# DAC_Wenzel.net
KiCad netlist of a schematic drawn in Altium Designer
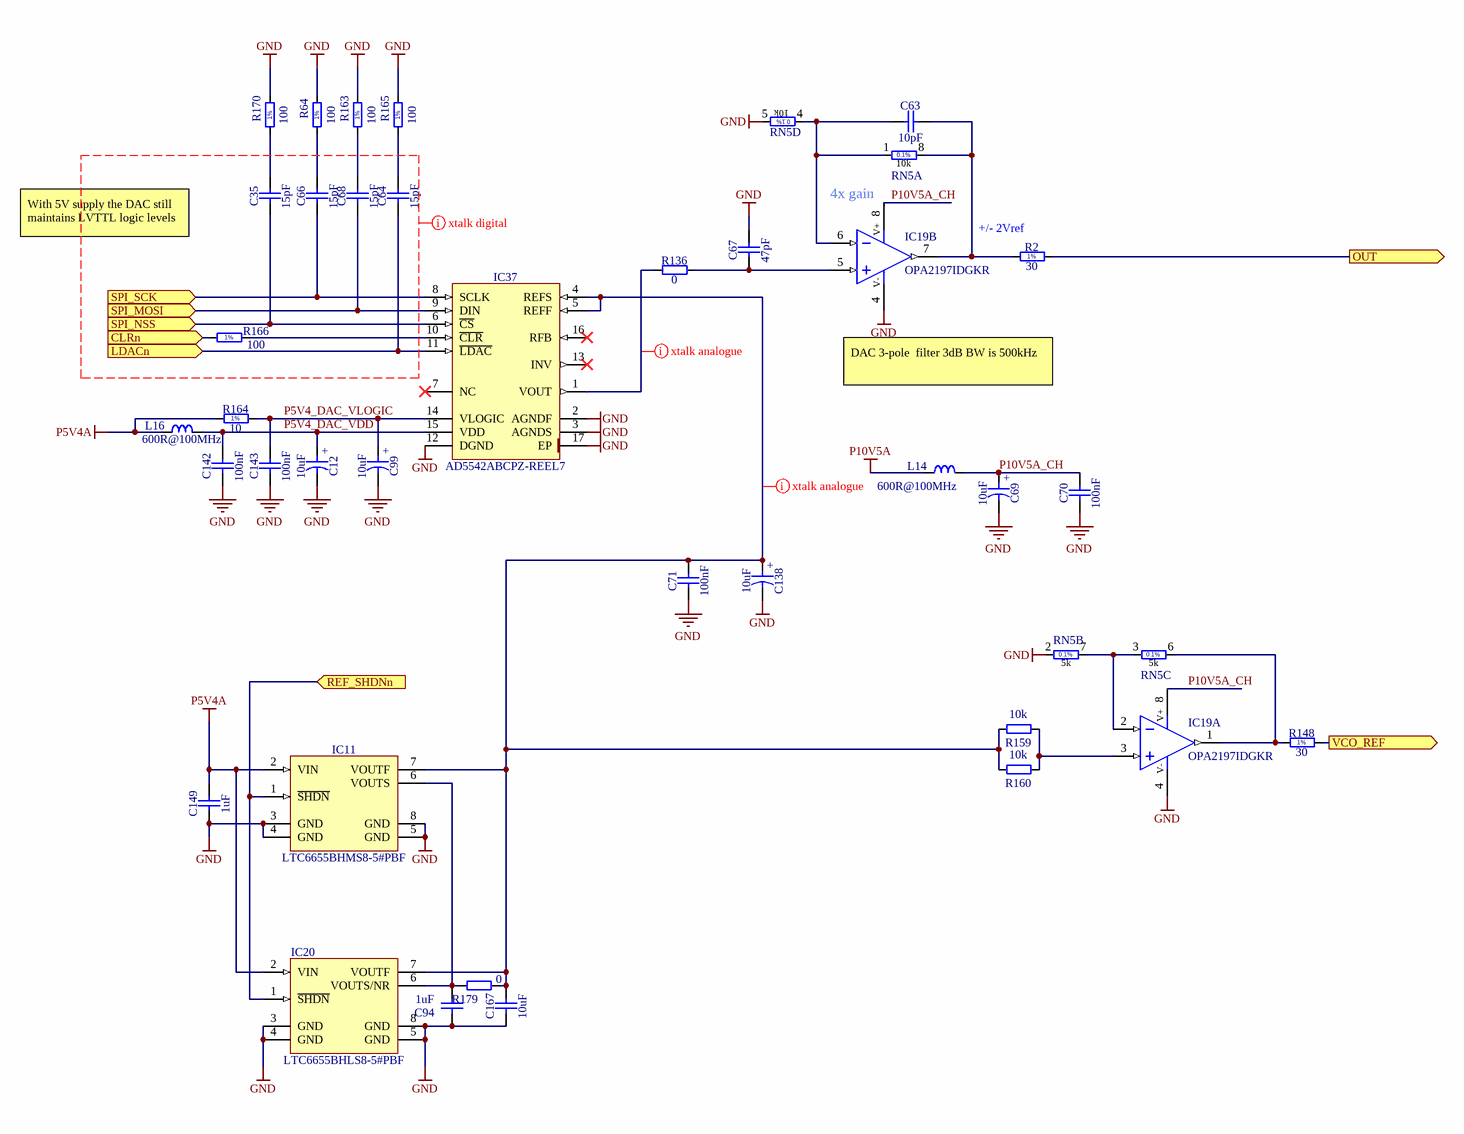
[diagram p0: DAC_Wenzel.SchDoc]

(export (version "E")
  (design (tool "Eeschema 10.0.6"))
  (components
    (comp (ref "C12")
      (value "10uF")
      (footprint "CAPMP3216X180N")
      (description "Polarised capacitor")
      (fields
        (field (name "PART NUMBER") "CTE3216-18_10UF_16V_20%_AVX_TCJ")
        (field (name "VOLTAGE") "16V")
        (field (name "AUTHOR") "CERN DEM JLC")
      )
      (libsource (lib "Capacitors") (part "Capacitor - polarized"))
    )
    (comp (ref "C35")
      (value "15pF")
      (footprint "CAPC1608X87N")
      (description "Non-polarised capacitor")
      (fields
        (field (name "PART NUMBER") "CC0603_15PF_50V_5%_NP0")
        (field (name "VOLTAGE") "50V")
        (field (name "AUTHOR") "CERN DEM JLC")
      )
      (libsource (lib "Capacitors") (part "Capacitor - non polarized"))
    )
    (comp (ref "C63")
      (value "10pF")
      (footprint "CAPC1005X55N")
      (description "Non-polarised capacitor")
      (fields
        (field (name "PART NUMBER") "CC0402_10PF_50V_5%_C0G")
        (field (name "VOLTAGE") "50V")
        (field (name "AUTHOR") "CERN DEM JLC")
      )
      (libsource (lib "Capacitors") (part "Capacitor - non polarized"))
    )
    (comp (ref "C64")
      (value "15pF")
      (footprint "CAPC1608X87N")
      (description "Non-polarised capacitor")
      (fields
        (field (name "PART NUMBER") "CC0603_15PF_50V_5%_NP0")
        (field (name "VOLTAGE") "50V")
        (field (name "AUTHOR") "CERN DEM JLC")
      )
      (libsource (lib "Capacitors") (part "Capacitor - non polarized"))
    )
    (comp (ref "C66")
      (value "15pF")
      (footprint "CAPC1608X87N")
      (description "Non-polarised capacitor")
      (fields
        (field (name "PART NUMBER") "CC0603_15PF_50V_5%_NP0")
        (field (name "VOLTAGE") "50V")
        (field (name "AUTHOR") "CERN DEM JLC")
      )
      (libsource (lib "Capacitors") (part "Capacitor - non polarized"))
    )
    (comp (ref "C67")
      (value "47pF")
      (footprint "CAPC1005X55N")
      (description "Non-polarised capacitor")
      (fields
        (field (name "PART NUMBER") "CC0402_47PF_50V_1%_C0G_MURATA_GJM1555C1H470FB01D")
        (field (name "VOLTAGE") "50V")
        (field (name "AUTHOR") "CERN DEM BC")
      )
      (libsource (lib "Capacitors") (part "Capacitor - non polarized"))
    )
    (comp (ref "C68")
      (value "15pF")
      (footprint "CAPC1608X87N")
      (description "Non-polarised capacitor")
      (fields
        (field (name "PART NUMBER") "CC0603_15PF_50V_5%_NP0")
        (field (name "VOLTAGE") "50V")
        (field (name "AUTHOR") "CERN DEM JLC")
      )
      (libsource (lib "Capacitors") (part "Capacitor - non polarized"))
    )
    (comp (ref "C69")
      (value "10uF")
      (footprint "CAPMP3216X180N")
      (description "Polarised capacitor")
      (fields
        (field (name "PART NUMBER") "CTE3216-18_10UF_16V_20%_AVX_TCJ")
        (field (name "VOLTAGE") "16V")
        (field (name "AUTHOR") "CERN DEM JLC")
      )
      (libsource (lib "Capacitors") (part "Capacitor - polarized"))
    )
    (comp (ref "C70")
      (value "100nF")
      (footprint "CAPC1005X55N")
      (description "Non-polarised capacitor")
      (fields
        (field (name "PART NUMBER") "CC0402_100NF_16V_10%_X7R")
        (field (name "VOLTAGE") "16V")
        (field (name "AUTHOR") "CERN DEM JLC")
      )
      (libsource (lib "Capacitors") (part "Capacitor - non polarized"))
    )
    (comp (ref "C71")
      (value "100nF")
      (footprint "CAPC1005X55N")
      (description "Non-polarised capacitor")
      (fields
        (field (name "PART NUMBER") "CC0402_100NF_16V_10%_X7R")
        (field (name "VOLTAGE") "16V")
        (field (name "AUTHOR") "CERN DEM JLC")
      )
      (libsource (lib "Capacitors") (part "Capacitor - non polarized"))
    )
    (comp (ref "C94")
      (value "1uF")
      (footprint "CAPC1608X87N")
      (description "Non-polarised capacitor")
      (fields
        (field (name "PART NUMBER") "CC0603_1UF_25V_10%_X7R")
        (field (name "VOLTAGE") "25V")
        (field (name "AUTHOR") "CERN DEM JLC")
      )
      (libsource (lib "Capacitors") (part "Capacitor - non polarized"))
    )
    (comp (ref "C99")
      (value "10uF")
      (footprint "CAPMP3216X180N")
      (description "Polarised capacitor")
      (fields
        (field (name "PART NUMBER") "CTE3216-18_10UF_16V_20%_AVX_TCJ")
        (field (name "VOLTAGE") "16V")
        (field (name "AUTHOR") "CERN DEM JLC")
      )
      (libsource (lib "Capacitors") (part "Capacitor - polarized"))
    )
    (comp (ref "C138")
      (value "10uF")
      (footprint "CAPMP3216X180N")
      (description "Polarised capacitor")
      (fields
        (field (name "PART NUMBER") "CTE3216-18_10UF_16V_20%_AVX_TCJ")
        (field (name "VOLTAGE") "16V")
        (field (name "AUTHOR") "CERN DEM JLC")
      )
      (libsource (lib "Capacitors") (part "Capacitor - polarized"))
    )
    (comp (ref "C142")
      (value "100nF")
      (footprint "CAPC1005X55N")
      (description "Non-polarised capacitor")
      (fields
        (field (name "PART NUMBER") "CC0402_100NF_16V_10%_X7R")
        (field (name "VOLTAGE") "16V")
        (field (name "AUTHOR") "CERN DEM JLC")
      )
      (libsource (lib "Capacitors") (part "Capacitor - non polarized"))
    )
    (comp (ref "C143")
      (value "100nF")
      (footprint "CAPC1005X55N")
      (description "Non-polarised capacitor")
      (fields
        (field (name "PART NUMBER") "CC0402_100NF_16V_10%_X7R")
        (field (name "VOLTAGE") "16V")
        (field (name "AUTHOR") "CERN DEM JLC")
      )
      (libsource (lib "Capacitors") (part "Capacitor - non polarized"))
    )
    (comp (ref "C149")
      (value "1uF")
      (footprint "CAPC1608X87N")
      (description "Non-polarised capacitor")
      (fields
        (field (name "PART NUMBER") "CC0603_1UF_25V_10%_X7R")
        (field (name "VOLTAGE") "25V")
        (field (name "AUTHOR") "CERN DEM JLC")
      )
      (libsource (lib "Capacitors") (part "Capacitor - non polarized"))
    )
    (comp (ref "C167")
      (value "10uF")
      (footprint "CAPC1608X80N")
      (description "Non-polarised capacitor")
      (fields
        (field (name "PART NUMBER") "CC0603_10UF_10V_10%_X5R")
        (field (name "VOLTAGE") "10V")
        (field (name "AUTHOR") "CERN DEM JLC")
      )
      (libsource (lib "Capacitors") (part "Capacitor - non polarized"))
    )
    (comp (ref "IC11")
      (value "LTC6655BHMS8-5#PBF")
      (footprint "SOP65P490X110-8N")
      (description "0.25ppm Noise, Low Drift Precision Buffered Voltage Reference")
      (fields (field (name "MANUFACTURER") "LINEAR TECHNOLOGY") (field (name "AUTHOR") "CERN DEM JLC"))
      (libsource (lib "ICs And Semiconductors") (part "LTC6655"))
    )
    (comp (ref "IC19")
      (value "OPA2197IDGKR")
      (footprint "SOP65P490X110-8N")
      (description "36-V, Precision, Rail-to-Rail Input Output, Low Offset Voltage Op Amp 8-VSSOP")
      (fields (field (name "MANUFACTURER") "TEXAS INSTRUMENTS") (field (name "AUTHOR") "GK"))
      (libsource (lib "ICs_Analog_Interfaces") (part "OA_OPA2197IDGKR"))
    )
    (comp (ref "IC20")
      (value "LTC6655BHLS8-5#PBF")
      (footprint "8-CLCC")
      (description "5.0V, 1uA Precision Voltage Reference")
      (fields (field (name "MANUFACTURER") "LINEAR TECHNOLOGY") (field (name "AUTHOR") "GK"))
      (libsource (lib "Sampler") (part "REF_LTC6655CHLS8-4.096"))
    )
    (comp (ref "IC37")
      (value "AD5542ABCPZ-REEL7")
      (footprint "QFN50P300X300X80-17N-S175")
      (description "2.7V to 5.5V, Serial-Input, Voltage-Output, 16-Bit DAC")
      (fields (field (name "MANUFACTURER") "ANALOG DEVICES") (field (name "AUTHOR") "CERN DEM JLC"))
      (libsource (lib "ICs And Semiconductors") (part "AD5542ABCPZ"))
    )
    (comp (ref "L14")
      (value "600R@100MHz")
      (footprint "INDC1005X55N")
      (description "Inductor")
      (fields
        (field (name "PART NUMBER") "IND0402_MURATA_BLM15HD601SN1")
        (field (name "POWER") "300mA")
        (field (name "AUTHOR") "CERN DEM JLC")
      )
      (libsource (lib "Inductors & Transformers") (part "Inductor"))
    )
    (comp (ref "L16")
      (value "600R@100MHz")
      (footprint "INDC1005X55N")
      (description "Inductor")
      (fields
        (field (name "PART NUMBER") "IND0402_MURATA_BLM15HD601SN1")
        (field (name "POWER") "300mA")
        (field (name "AUTHOR") "CERN DEM JLC")
      )
      (libsource (lib "Inductors & Transformers") (part "Inductor"))
    )
    (comp (ref "R2")
      (value "30")
      (footprint "RESC1608X55N")
      (description "Resistor - 1%")
      (fields
        (field (name "PART NUMBER") "R0603_30R_1%_0.1W_100PPM")
        (field (name "POWER") "0.1W")
        (field (name "AUTHOR") "CERN DEM JLC")
      )
      (libsource (lib "Resistors") (part "Resistor - 1%"))
    )
    (comp (ref "R64")
      (value "100")
      (footprint "RESC1005X40N")
      (description "Resistor - 1%")
      (fields
        (field (name "PART NUMBER") "R0402_100R_1%_0.0625W_100PPM")
        (field (name "POWER") "0.0625W")
        (field (name "AUTHOR") "CERN DEM JLC")
      )
      (libsource (lib "Resistors") (part "Resistor - 1%"))
    )
    (comp (ref "R136")
      (value "0")
      (footprint "RESC1005X40N")
      (description "Resistor")
      (fields
        (field (name "PART NUMBER") "R0402_0R_JUMPER")
        (field (name "MANUFACTURER") "GENERIC")
        (field (name "AUTHOR") "CERN DEM JLC")
      )
      (libsource (lib "Resistors") (part "Resistor"))
    )
    (comp (ref "R148")
      (value "30")
      (footprint "RESC1608X55N")
      (description "Resistor - 1%")
      (fields
        (field (name "PART NUMBER") "R0603_30R_1%_0.1W_100PPM")
        (field (name "POWER") "0.1W")
        (field (name "AUTHOR") "CERN DEM JLC")
      )
      (libsource (lib "Resistors") (part "Resistor - 1%"))
    )
    (comp (ref "R159")
      (value "10k")
      (footprint "RESC1608X55N")
      (description "Resistor - 1%")
      (fields
        (field (name "PART NUMBER") "R0603_10K_1%_0.1W_100PPM")
        (field (name "POWER") "0.1W")
        (field (name "AUTHOR") "CERN DEM JLC")
      )
      (libsource (lib "") (part "Resistor - 1%_1"))
    )
    (comp (ref "R160")
      (value "10k")
      (footprint "RESC1608X55N")
      (description "Resistor - 1%")
      (fields
        (field (name "PART NUMBER") "R0603_10K_1%_0.1W_100PPM")
        (field (name "POWER") "0.1W")
        (field (name "AUTHOR") "CERN DEM JLC")
      )
      (libsource (lib "") (part "Resistor - 1%_1"))
    )
    (comp (ref "R163")
      (value "100")
      (footprint "RESC1005X40N")
      (description "Resistor - 1%")
      (fields
        (field (name "PART NUMBER") "R0402_100R_1%_0.0625W_100PPM")
        (field (name "POWER") "0.0625W")
        (field (name "AUTHOR") "CERN DEM JLC")
      )
      (libsource (lib "Resistors") (part "Resistor - 1%"))
    )
    (comp (ref "R164")
      (value "10")
      (footprint "RESC1005X40N")
      (description "Resistor - 1%")
      (fields
        (field (name "PART NUMBER") "R0402_10R_1%_0.0625W_200PPM")
        (field (name "POWER") "0.0625W")
        (field (name "AUTHOR") "CERN DEM JLC")
      )
      (libsource (lib "Resistors") (part "Resistor - 1%"))
    )
    (comp (ref "R165")
      (value "100")
      (footprint "RESC1005X40N")
      (description "Resistor - 1%")
      (fields
        (field (name "PART NUMBER") "R0402_100R_1%_0.0625W_100PPM")
        (field (name "POWER") "0.0625W")
        (field (name "AUTHOR") "CERN DEM JLC")
      )
      (libsource (lib "Resistors") (part "Resistor - 1%"))
    )
    (comp (ref "R166")
      (value "100")
      (footprint "RESC1005X40N")
      (description "Resistor - 1%")
      (fields
        (field (name "PART NUMBER") "R0402_100R_1%_0.0625W_100PPM")
        (field (name "POWER") "0.0625W")
        (field (name "AUTHOR") "CERN DEM JLC")
      )
      (libsource (lib "Resistors") (part "Resistor - 1%"))
    )
    (comp (ref "R170")
      (value "100")
      (footprint "RESC1005X40N")
      (description "Resistor - 1%")
      (fields
        (field (name "PART NUMBER") "R0402_100R_1%_0.0625W_100PPM")
        (field (name "POWER") "0.0625W")
        (field (name "AUTHOR") "CERN DEM JLC")
      )
      (libsource (lib "Resistors") (part "Resistor - 1%"))
    )
    (comp (ref "R179")
      (value "0")
      (footprint "RESC1005X40N")
      (description "Resistor")
      (fields
        (field (name "PART NUMBER") "R0402_0R_JUMPER")
        (field (name "MANUFACTURER") "GENERIC")
        (field (name "AUTHOR") "CERN DEM JLC")
      )
      (libsource (lib "Resistors") (part "Resistor"))
    )
    (comp (ref "RN5")
      (value "10k 5K 5K 10K")
      (footprint "SOIC127P600X175-8N")
      (description "DIL8 Resistor Network 4 Resistors 10k-5k-5k-10k 0.1%")
      (fields
        (field (name "PART NUMBER") "RN_10K_5K_VISHAY_AORN2-1AT3")
        (field (name "POWER") "4x0.1W")
        (field (name "AUTHOR") "CERN DEM JLC")
      )
      (libsource (lib "Resistors") (part "RN DIL8_4xR_10k-5k-5k-10k_0.1%"))
    )
  )
  (nets
    (net (code "1") (name "/CLRn") (class "Default")
      (node (ref "R166") (pin "1") (pinfunction "1_1") (pintype "passive"))
    )
    (net (code "2") (name "/LDACn") (class "Default")
      (node (ref "C64") (pin "1") (pinfunction "1_1") (pintype "passive"))
      (node (ref "IC37") (pin "11") (pinfunction "~{LDAC}_11") (pintype "input"))
    )
    (net (code "3") (name "/OUT") (class "Default")
      (node (ref "R2") (pin "2") (pinfunction "2_2") (pintype "passive"))
    )
    (net (code "4") (name "/P5V4_DAC_VDD") (class "Default")
      (node (ref "C12") (pin "1") (pinfunction "1_1") (pintype "passive"))
      (node (ref "C142") (pin "2") (pinfunction "2_2") (pintype "passive"))
      (node (ref "IC37") (pin "15") (pinfunction "VDD_15") (pintype "power_in"))
      (node (ref "L16") (pin "2") (pinfunction "2_2") (pintype "passive"))
    )
    (net (code "5") (name "/P5V4_DAC_VLOGIC") (class "Default")
      (node (ref "C143") (pin "2") (pinfunction "2_2") (pintype "passive"))
      (node (ref "C99") (pin "1") (pinfunction "1_1") (pintype "passive"))
      (node (ref "IC37") (pin "14") (pinfunction "VLOGIC_14") (pintype "power_in"))
      (node (ref "R164") (pin "2") (pinfunction "2_2") (pintype "passive"))
    )
    (net (code "6") (name "/P10V5A_CH") (class "Default")
      (node (ref "C69") (pin "1") (pinfunction "1_1") (pintype "passive"))
      (node (ref "C70") (pin "2") (pinfunction "2_2") (pintype "passive"))
      (node (ref "IC19") (pin "8") (pinfunction "V+_8") (pintype "power_in"))
      (node (ref "L14") (pin "2") (pinfunction "2_2") (pintype "passive"))
    )
    (net (code "7") (name "/REF_SHDNn") (class "Default")
      (node (ref "IC11") (pin "1") (pinfunction "~{SHDN}_1") (pintype "input"))
      (node (ref "IC20") (pin "1") (pinfunction "~{SHDN}_1") (pintype "input"))
    )
    (net (code "8") (name "/SPI_MOSI") (class "Default")
      (node (ref "C68") (pin "1") (pinfunction "1_1") (pintype "passive"))
      (node (ref "IC37") (pin "9") (pinfunction "DIN_9") (pintype "input"))
    )
    (net (code "9") (name "/SPI_NSS") (class "Default")
      (node (ref "C35") (pin "1") (pinfunction "1_1") (pintype "passive"))
      (node (ref "IC37") (pin "6") (pinfunction "~{CS}_6") (pintype "input"))
    )
    (net (code "10") (name "/SPI_SCK") (class "Default")
      (node (ref "C66") (pin "1") (pinfunction "1_1") (pintype "passive"))
      (node (ref "IC37") (pin "8") (pinfunction "SCLK_8") (pintype "input"))
    )
    (net (code "11") (name "/VCO_REF") (class "Default")
      (node (ref "R148") (pin "2") (pinfunction "2_2") (pintype "passive"))
    )
    (net (code "12") (name "GND") (class "Default")
      (node (ref "C12") (pin "2") (pinfunction "2_2") (pintype "passive"))
      (node (ref "C138") (pin "2") (pinfunction "2_2") (pintype "passive"))
      (node (ref "C142") (pin "1") (pinfunction "1_1") (pintype "passive"))
      (node (ref "C143") (pin "1") (pinfunction "1_1") (pintype "passive"))
      (node (ref "C149") (pin "1") (pinfunction "1_1") (pintype "passive"))
      (node (ref "C167") (pin "1") (pinfunction "1_1") (pintype "passive"))
      (node (ref "C67") (pin "2") (pinfunction "2_2") (pintype "passive"))
      (node (ref "C69") (pin "2") (pinfunction "2_2") (pintype "passive"))
      (node (ref "C70") (pin "1") (pinfunction "1_1") (pintype "passive"))
      (node (ref "C71") (pin "1") (pinfunction "1_1") (pintype "passive"))
      (node (ref "C94") (pin "1") (pinfunction "1_1") (pintype "passive"))
      (node (ref "C99") (pin "2") (pinfunction "2_2") (pintype "passive"))
      (node (ref "IC11") (pin "3") (pinfunction "GND_3") (pintype "power_in"))
      (node (ref "IC11") (pin "4") (pinfunction "GND_4") (pintype "power_in"))
      (node (ref "IC11") (pin "5") (pinfunction "GND_5") (pintype "power_in"))
      (node (ref "IC11") (pin "8") (pinfunction "GND_8") (pintype "power_in"))
      (node (ref "IC19") (pin "4") (pinfunction "V-_4") (pintype "power_in"))
      (node (ref "IC20") (pin "3") (pinfunction "GND_3") (pintype "power_in"))
      (node (ref "IC20") (pin "4") (pinfunction "GND_4") (pintype "power_in"))
      (node (ref "IC20") (pin "5") (pinfunction "GND_5") (pintype "power_in"))
      (node (ref "IC20") (pin "8") (pinfunction "GND_8") (pintype "power_in"))
      (node (ref "IC37") (pin "12") (pinfunction "DGND_12") (pintype "power_in"))
      (node (ref "IC37") (pin "17") (pinfunction "EP_17") (pintype "power_in"))
      (node (ref "IC37") (pin "2") (pinfunction "AGNDF_2") (pintype "power_in"))
      (node (ref "IC37") (pin "3") (pinfunction "AGNDS_3") (pintype "power_in"))
      (node (ref "R163") (pin "2") (pinfunction "2_2") (pintype "passive"))
      (node (ref "R165") (pin "2") (pinfunction "2_2") (pintype "passive"))
      (node (ref "R170") (pin "2") (pinfunction "2_2") (pintype "passive"))
      (node (ref "R64") (pin "2") (pinfunction "2_2") (pintype "passive"))
      (node (ref "RN5") (pin "2") (pinfunction "2_2") (pintype "passive"))
      (node (ref "RN5") (pin "5") (pinfunction "5_5") (pintype "passive"))
    )
    (net (code "13") (name "Net-(C35-Pad2)") (class "Default")
      (node (ref "C35") (pin "2") (pinfunction "2_2") (pintype "passive"))
      (node (ref "R170") (pin "1") (pinfunction "1_1") (pintype "passive"))
    )
    (net (code "14") (name "Net-(C64-Pad2)") (class "Default")
      (node (ref "C64") (pin "2") (pinfunction "2_2") (pintype "passive"))
      (node (ref "R165") (pin "1") (pinfunction "1_1") (pintype "passive"))
    )
    (net (code "15") (name "Net-(C66-Pad2)") (class "Default")
      (node (ref "C66") (pin "2") (pinfunction "2_2") (pintype "passive"))
      (node (ref "R64") (pin "1") (pinfunction "1_1") (pintype "passive"))
    )
    (net (code "16") (name "Net-(C68-Pad2)") (class "Default")
      (node (ref "C68") (pin "2") (pinfunction "2_2") (pintype "passive"))
      (node (ref "R163") (pin "1") (pinfunction "1_1") (pintype "passive"))
    )
    (net (code "17") (name "Net-(IC11-VOUTF)") (class "Default")
      (node (ref "C138") (pin "1") (pinfunction "1_1") (pintype "passive"))
      (node (ref "C167") (pin "2") (pinfunction "2_2") (pintype "passive"))
      (node (ref "C71") (pin "2") (pinfunction "2_2") (pintype "passive"))
      (node (ref "IC11") (pin "7") (pinfunction "VOUTF_7") (pintype "power_in"))
      (node (ref "IC20") (pin "7") (pinfunction "VOUTF_7") (pintype "power_in"))
      (node (ref "IC37") (pin "4") (pinfunction "REFS_4") (pintype "input"))
      (node (ref "IC37") (pin "5") (pinfunction "REFF_5") (pintype "input"))
      (node (ref "R159") (pin "2") (pinfunction "2_2") (pintype "passive"))
      (node (ref "R160") (pin "2") (pinfunction "2_2") (pintype "passive"))
      (node (ref "R179") (pin "2") (pinfunction "2_2") (pintype "passive"))
    )
    (net (code "18") (name "Net-(IC11-VOUTS)") (class "Default")
      (node (ref "C94") (pin "2") (pinfunction "2_2") (pintype "passive"))
      (node (ref "IC11") (pin "6") (pinfunction "VOUTS_6") (pintype "power_in"))
      (node (ref "IC20") (pin "6") (pinfunction "VOUTS/NR_6") (pintype "power_in"))
      (node (ref "R179") (pin "1") (pinfunction "1_1") (pintype "passive"))
    )
    (net (code "19") (name "Net-(IC19A-IN+)") (class "Default")
      (node (ref "IC19") (pin "3") (pinfunction "IN+_3") (pintype "input"))
      (node (ref "R159") (pin "1") (pinfunction "1_1") (pintype "passive"))
      (node (ref "R160") (pin "1") (pinfunction "1_1") (pintype "passive"))
    )
    (net (code "20") (name "Net-(IC19A-IN-)") (class "Default")
      (node (ref "IC19") (pin "2") (pinfunction "IN-_2") (pintype "input"))
      (node (ref "RN5") (pin "3") (pinfunction "3_3") (pintype "passive"))
      (node (ref "RN5") (pin "7") (pinfunction "7_7") (pintype "passive"))
    )
    (net (code "21") (name "Net-(IC19A-OUT)") (class "Default")
      (node (ref "IC19") (pin "1") (pinfunction "OUT_1") (pintype "output"))
      (node (ref "R148") (pin "1") (pinfunction "1_1") (pintype "passive"))
      (node (ref "RN5") (pin "6") (pinfunction "6_6") (pintype "passive"))
    )
    (net (code "22") (name "Net-(IC19B-IN+)") (class "Default")
      (node (ref "C67") (pin "1") (pinfunction "1_1") (pintype "passive"))
      (node (ref "IC19") (pin "5") (pinfunction "IN+_5") (pintype "input"))
      (node (ref "R136") (pin "2") (pinfunction "2_2") (pintype "passive"))
    )
    (net (code "23") (name "Net-(IC19B-IN-)") (class "Default")
      (node (ref "C63") (pin "1") (pinfunction "1_1") (pintype "passive"))
      (node (ref "IC19") (pin "6") (pinfunction "IN-_6") (pintype "input"))
      (node (ref "RN5") (pin "1") (pinfunction "1_1") (pintype "passive"))
      (node (ref "RN5") (pin "4") (pinfunction "4_4") (pintype "passive"))
    )
    (net (code "24") (name "Net-(IC19B-OUT)") (class "Default")
      (node (ref "C63") (pin "2") (pinfunction "2_2") (pintype "passive"))
      (node (ref "IC19") (pin "7") (pinfunction "OUT_7") (pintype "output"))
      (node (ref "R2") (pin "1") (pinfunction "1_1") (pintype "passive"))
      (node (ref "RN5") (pin "8") (pinfunction "8_8") (pintype "passive"))
    )
    (net (code "25") (name "Net-(IC37-VOUT)") (class "Default")
      (node (ref "IC37") (pin "1") (pinfunction "VOUT_1") (pintype "output"))
      (node (ref "R136") (pin "1") (pinfunction "1_1") (pintype "passive"))
    )
    (net (code "26") (name "Net-(IC37-~{CLR})") (class "Default")
      (node (ref "IC37") (pin "10") (pinfunction "~{CLR}_10") (pintype "input"))
      (node (ref "R166") (pin "2") (pinfunction "2_2") (pintype "passive"))
    )
    (net (code "27") (name "P5V4A") (class "Default")
      (node (ref "C149") (pin "2") (pinfunction "2_2") (pintype "passive"))
      (node (ref "IC11") (pin "2") (pinfunction "VIN_2") (pintype "input"))
      (node (ref "IC20") (pin "2") (pinfunction "VIN_2") (pintype "input"))
      (node (ref "L16") (pin "1") (pinfunction "1_1") (pintype "passive"))
      (node (ref "R164") (pin "1") (pinfunction "1_1") (pintype "passive"))
    )
    (net (code "28") (name "P10V5A") (class "Default")
      (node (ref "L14") (pin "1") (pinfunction "1_1") (pintype "passive"))
    )
    (net (code "29") (name "unconnected-(IC37-INV-Pad13)") (class "Default")
      (node (ref "IC37") (pin "13") (pinfunction "INV_13") (pintype "output+no_connect"))
    )
    (net (code "30") (name "unconnected-(IC37-NC-Pad7)") (class "Default")
      (node (ref "IC37") (pin "7") (pinfunction "NC_7") (pintype "passive+no_connect"))
    )
    (net (code "31") (name "unconnected-(IC37-RFB-Pad16)") (class "Default")
      (node (ref "IC37") (pin "16") (pinfunction "RFB_16") (pintype "input+no_connect"))
    )
  )
)
